# 2021-06-02.net
KiCad netlist of a schematic drawn in EasyEDA
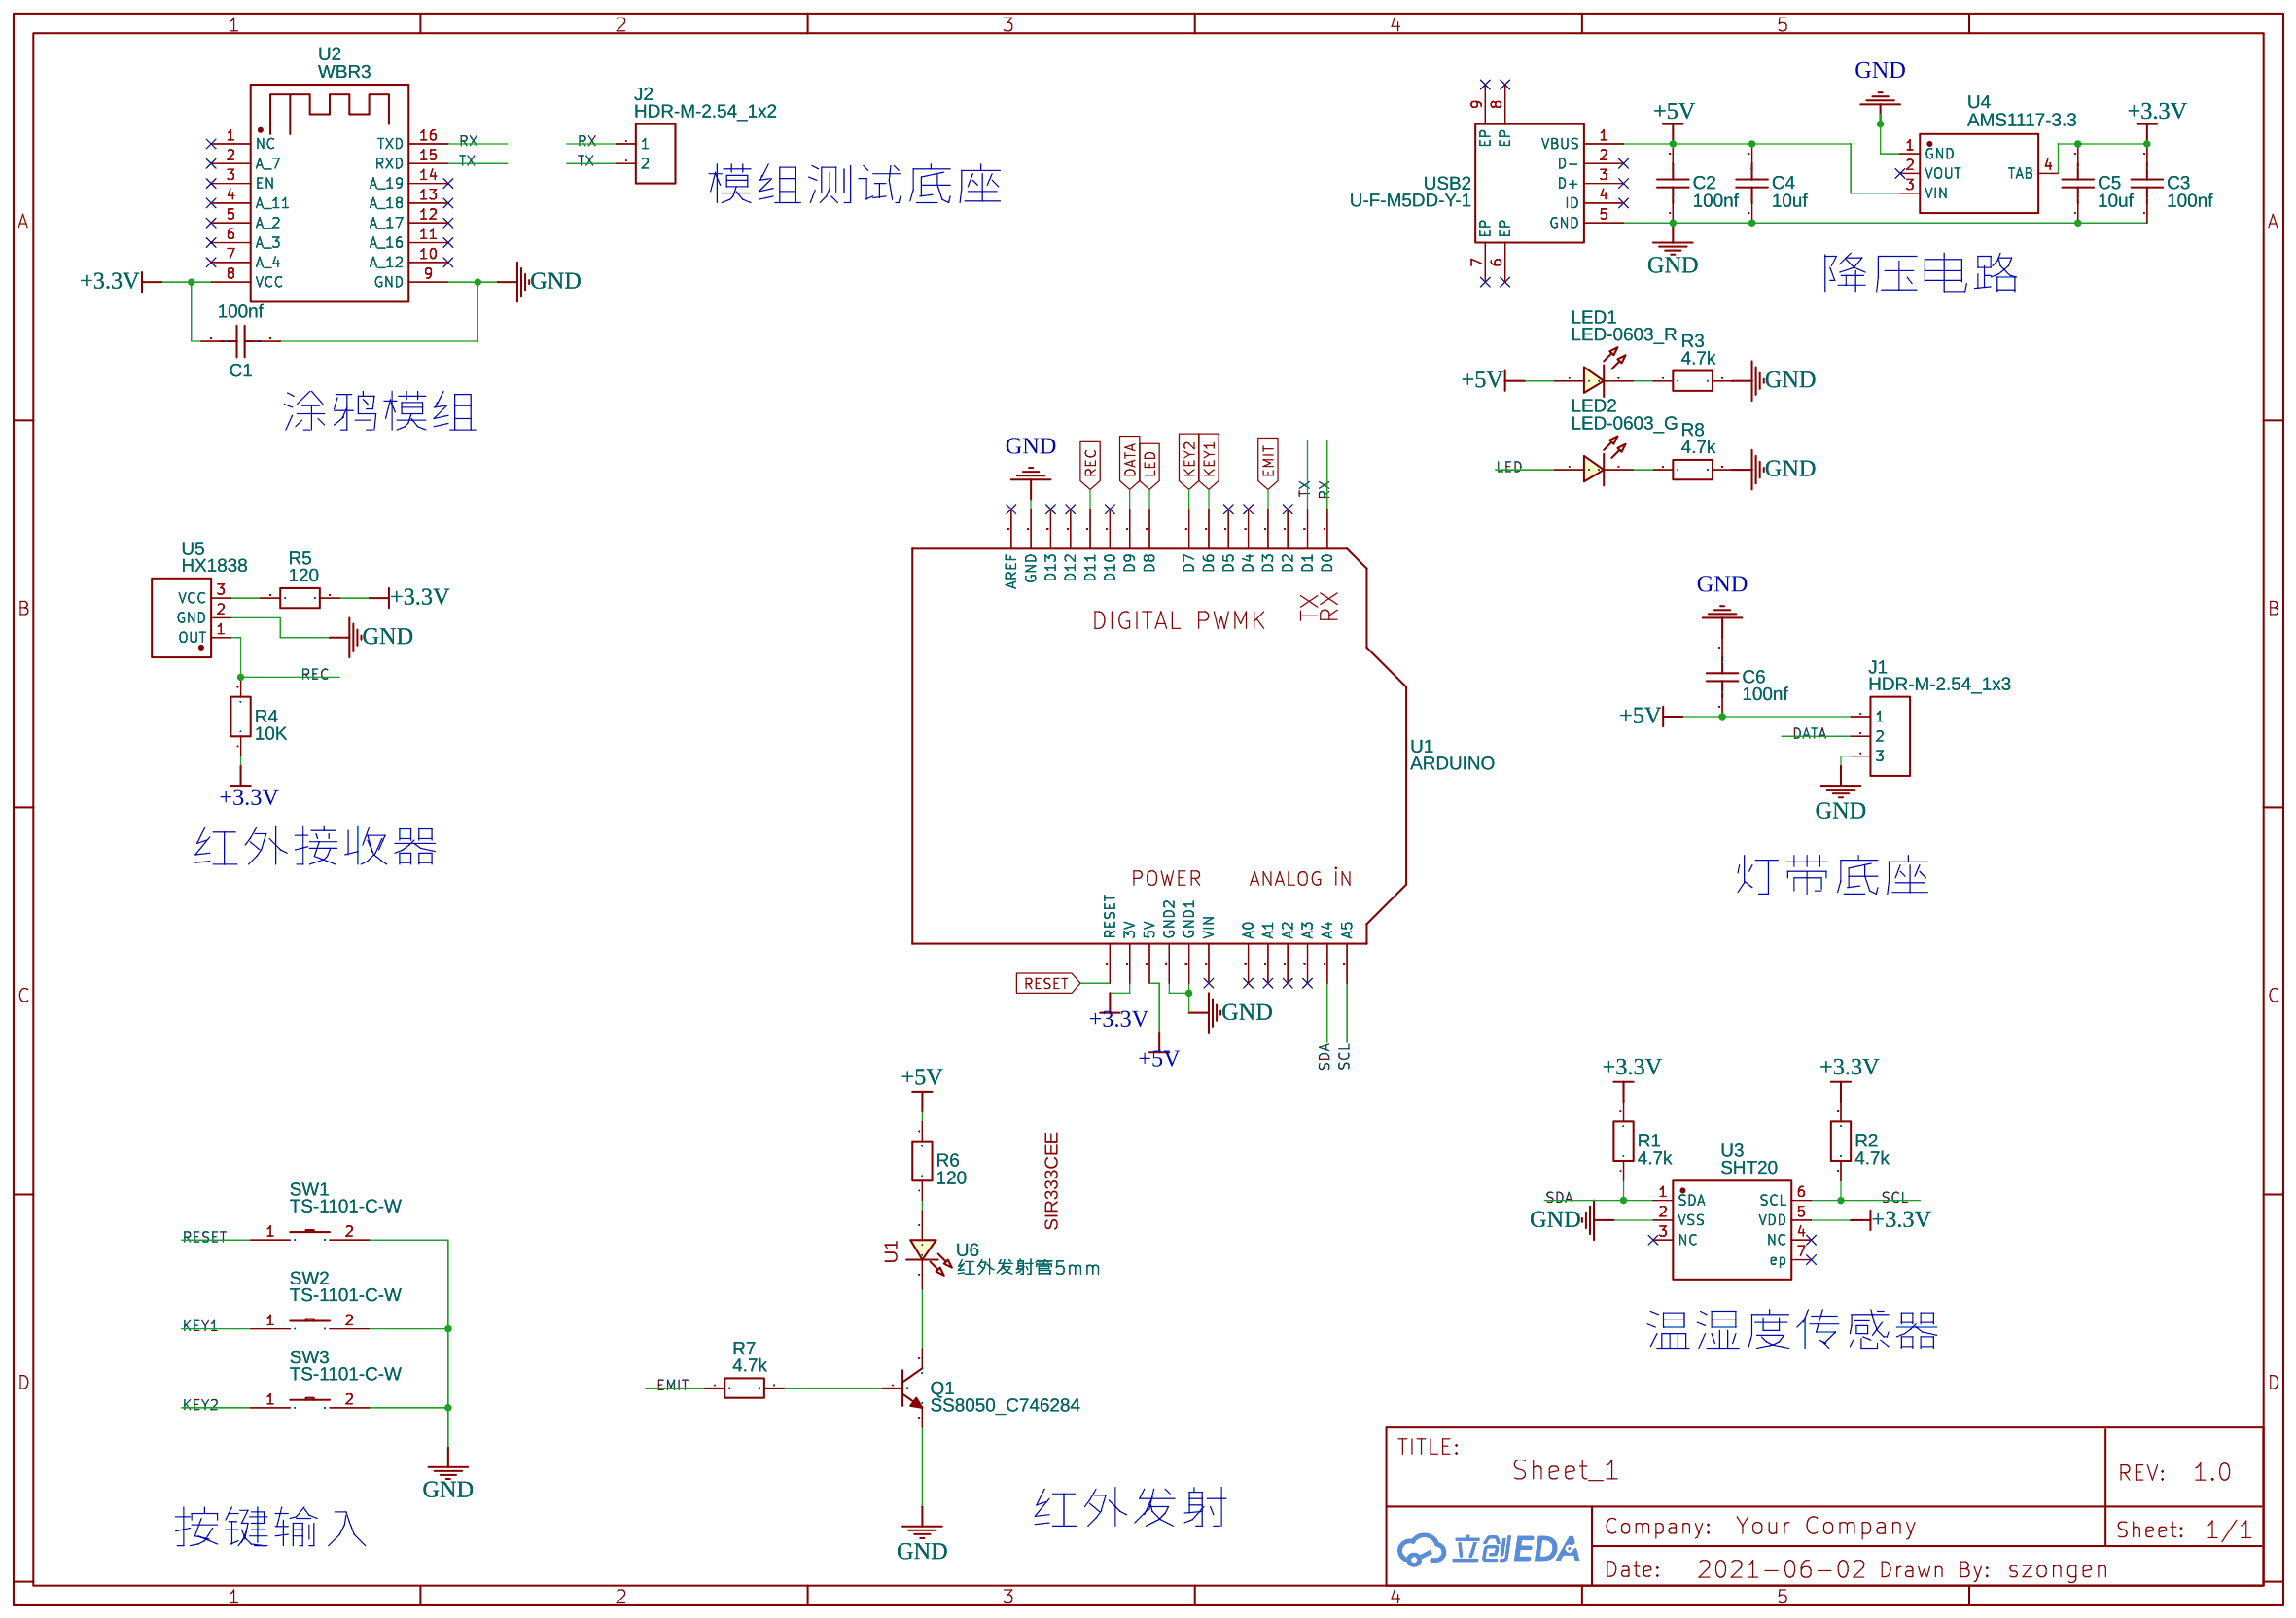
[diagram p0: schematic sheet]

(export (version "E")
  (design (tool "Eeschema 10.0.6"))
  (components
    (comp (ref "C1") (value "100nf") (libsource (lib "") (part "C_0603_US_1")))
    (comp (ref "C2") (value "100nf") (libsource (lib "") (part "C_0603_US")))
    (comp (ref "C3") (value "100nf") (libsource (lib "") (part "C_0603_US")))
    (comp (ref "C4") (value "10uf") (libsource (lib "") (part "C_0603_US")))
    (comp (ref "C5") (value "10uf") (libsource (lib "") (part "C_0603_US")))
    (comp (ref "C6") (value "100nf") (libsource (lib "") (part "C_0603_US")))
    (comp (ref "J1")
      (value "HDR-M-2.54_1x3")
      (fields (field (name "BOM_Supplier Part") "C180248"))
      (libsource (lib "") (part "HDR-M-2.54_1x3"))
    )
    (comp (ref "J2")
      (value "HDR-M-2.54_1x2")
      (fields (field (name "BOM_Supplier Part") "C124375"))
      (libsource (lib "") (part "HDR-M-2.54_1x2"))
    )
    (comp (ref "LED1")
      (value "LED-0603_R")
      (fields
        (field (name "BOM_Manufacturer Part") "19-217/R6C-AL1M2VY/3T")
        (field (name "BOM_Supplier Part") "C72044")
      )
      (libsource (lib "") (part "LED-0603_R"))
    )
    (comp (ref "LED2")
      (value "LED-0603_G")
      (fields
        (field (name "BOM_Manufacturer Part") "19-217/GHC-YR1S2/3T")
        (field (name "BOM_Supplier Part") "C72043")
      )
      (libsource (lib "") (part "LED-0603_G"))
    )
    (comp (ref "Q1")
      (value "SS8050_C746284")
      (fields (field (name "BOM_Manufacturer Part") "SS8050") (field (name "BOM_Supplier Part") "C746284"))
      (libsource (lib "") (part "SS8050_C746284"))
    )
    (comp (ref "R1") (value "4.7k") (libsource (lib "") (part "R_0603_EU_1")))
    (comp (ref "R2") (value "4.7k") (libsource (lib "") (part "R_0603_EU_1")))
    (comp (ref "R3") (value "4.7k") (libsource (lib "") (part "R_0603_EU")))
    (comp (ref "R4") (value "10K") (libsource (lib "") (part "R_0805_EU_1")))
    (comp (ref "R5") (value "120") (libsource (lib "") (part "R_0805_EU")))
    (comp (ref "R6") (value "120") (libsource (lib "") (part "R_0805_EU_1")))
    (comp (ref "R7") (value "4.7k") (libsource (lib "") (part "R_0805_EU")))
    (comp (ref "R8") (value "4.7k") (libsource (lib "") (part "R_0603_EU")))
    (comp (ref "SW1")
      (value "TS-1101-C-W")
      (fields (field (name "BOM_Supplier Part") "C318938"))
      (libsource (lib "") (part "TS-1101-C-W"))
    )
    (comp (ref "SW2")
      (value "TS-1101-C-W")
      (fields (field (name "BOM_Supplier Part") "C318938"))
      (libsource (lib "") (part "TS-1101-C-W"))
    )
    (comp (ref "SW3")
      (value "TS-1101-C-W")
      (fields (field (name "BOM_Supplier Part") "C318938"))
      (libsource (lib "") (part "TS-1101-C-W"))
    )
    (comp (ref "U1") (value "ARDUINO") (libsource (lib "") (part "ARDUINO")))
    (comp (ref "U2") (value "WBR3") (libsource (lib "") (part "WBR3")))
    (comp (ref "U3")
      (value "SHT20")
      (fields (field (name "BOM_Supplier Part") "C53865"))
      (libsource (lib "") (part "SHT20"))
    )
    (comp (ref "U4")
      (value "AMS1117-3.3")
      (fields (field (name "BOM_Supplier Part") "C351784"))
      (libsource (lib "") (part "AMS1117-3.3_C351784"))
    )
    (comp (ref "U5")
      (value "HX1838")
      (fields (field (name "BOM_Manufacturer Part") "0"))
      (libsource (lib "") (part "HX1838"))
    )
    (comp (ref "U6") (value "红外发射管5mm") (libsource (lib "") (part "红外发射管5mm")))
    (comp (ref "USB2")
      (value "U-F-M5DD-Y-1")
      (fields (field (name "BOM_Supplier Part") "C91467"))
      (libsource (lib "") (part "U-F-M5DD-Y-1"))
    )
  )
  (nets
    (net (code "1") (name "+3.3V") (class "Default")
      (node (ref "C1") (pin "1") (pinfunction "1_1") (pintype "unspecified"))
      (node (ref "C3") (pin "2") (pinfunction "2_2") (pintype "unspecified"))
      (node (ref "C5") (pin "2") (pinfunction "2_2") (pintype "unspecified"))
      (node (ref "R1") (pin "2") (pinfunction "2_2") (pintype "unspecified"))
      (node (ref "R2") (pin "2") (pinfunction "2_2") (pintype "unspecified"))
      (node (ref "R4") (pin "1") (pinfunction "1_1") (pintype "unspecified"))
      (node (ref "R5") (pin "2") (pinfunction "2_2") (pintype "unspecified"))
      (node (ref "U1") (pin "3V") (pinfunction "3V_3V") (pintype "passive"))
      (node (ref "U2") (pin "8") (pinfunction "VCC_8") (pintype "unspecified"))
      (node (ref "U3") (pin "5") (pinfunction "VDD_5") (pintype "unspecified"))
      (node (ref "U4") (pin "4") (pinfunction "TAB_4") (pintype "unspecified"))
    )
    (net (code "2") (name "+5V") (class "Default")
      (node (ref "C2") (pin "2") (pinfunction "2_2") (pintype "unspecified"))
      (node (ref "C4") (pin "2") (pinfunction "2_2") (pintype "unspecified"))
      (node (ref "C6") (pin "1") (pinfunction "1_1") (pintype "unspecified"))
      (node (ref "J1") (pin "1") (pinfunction "1_1") (pintype "input"))
      (node (ref "LED1") (pin "1") (pinfunction "1_1") (pintype "unspecified"))
      (node (ref "R6") (pin "2") (pinfunction "2_2") (pintype "unspecified"))
      (node (ref "U1") (pin "5V") (pinfunction "5V_5V") (pintype "passive"))
      (node (ref "U4") (pin "3") (pinfunction "VIN_3") (pintype "unspecified"))
      (node (ref "USB2") (pin "1") (pinfunction "VBUS_1") (pintype "unspecified"))
    )
    (net (code "3") (name "/RX") (class "Default")
      (node (ref "J2") (pin "1") (pinfunction "1_1") (pintype "unspecified"))
      (node (ref "U1") (pin "D0") (pinfunction "D0_D0") (pintype "unspecified"))
      (node (ref "U2") (pin "16") (pinfunction "TXD_16") (pintype "unspecified"))
    )
    (net (code "4") (name "/SCL") (class "Default")
      (node (ref "R2") (pin "1") (pinfunction "1_1") (pintype "unspecified"))
      (node (ref "U1") (pin "A5") (pinfunction "A5_A5") (pintype "unspecified"))
      (node (ref "U3") (pin "6") (pinfunction "SCL_6") (pintype "unspecified"))
    )
    (net (code "5") (name "/SDA") (class "Default")
      (node (ref "R1") (pin "1") (pinfunction "1_1") (pintype "unspecified"))
      (node (ref "U1") (pin "A4") (pinfunction "A4_A4") (pintype "unspecified"))
      (node (ref "U3") (pin "1") (pinfunction "SDA_1") (pintype "unspecified"))
    )
    (net (code "6") (name "/TX") (class "Default")
      (node (ref "J2") (pin "2") (pinfunction "2_2") (pintype "unspecified"))
      (node (ref "U1") (pin "D1") (pinfunction "D1_D1") (pintype "unspecified"))
      (node (ref "U2") (pin "15") (pinfunction "RXD_15") (pintype "unspecified"))
    )
    (net (code "7") (name "DATA") (class "Default")
      (node (ref "J1") (pin "2") (pinfunction "2_2") (pintype "input"))
      (node (ref "U1") (pin "D9") (pinfunction "D9_D9") (pintype "unspecified"))
    )
    (net (code "8") (name "EMIT") (class "Default")
      (node (ref "R7") (pin "1") (pinfunction "1_1") (pintype "unspecified"))
      (node (ref "U1") (pin "D3") (pinfunction "D3_D3") (pintype "unspecified"))
    )
    (net (code "9") (name "GND") (class "Default")
      (node (ref "C1") (pin "2") (pinfunction "2_2") (pintype "unspecified"))
      (node (ref "C2") (pin "1") (pinfunction "1_1") (pintype "unspecified"))
      (node (ref "C3") (pin "1") (pinfunction "1_1") (pintype "unspecified"))
      (node (ref "C4") (pin "1") (pinfunction "1_1") (pintype "unspecified"))
      (node (ref "C5") (pin "1") (pinfunction "1_1") (pintype "unspecified"))
      (node (ref "C6") (pin "2") (pinfunction "2_2") (pintype "unspecified"))
      (node (ref "J1") (pin "3") (pinfunction "3_3") (pintype "input"))
      (node (ref "Q1") (pin "2") (pinfunction "E_2") (pintype "unspecified"))
      (node (ref "R3") (pin "2") (pinfunction "2_2") (pintype "unspecified"))
      (node (ref "R8") (pin "2") (pinfunction "2_2") (pintype "unspecified"))
      (node (ref "SW1") (pin "2") (pinfunction "2_2") (pintype "unspecified"))
      (node (ref "SW2") (pin "2") (pinfunction "2_2") (pintype "unspecified"))
      (node (ref "SW3") (pin "2") (pinfunction "2_2") (pintype "unspecified"))
      (node (ref "U1") (pin "GND") (pinfunction "GND_GND") (pintype "passive"))
      (node (ref "U1") (pin "GND1") (pinfunction "GND1_GND1") (pintype "passive"))
      (node (ref "U1") (pin "GND2") (pinfunction "GND2_GND2") (pintype "passive"))
      (node (ref "U2") (pin "9") (pinfunction "GND_9") (pintype "unspecified"))
      (node (ref "U3") (pin "2") (pinfunction "VSS_2") (pintype "unspecified"))
      (node (ref "U4") (pin "1") (pinfunction "GND_1") (pintype "unspecified"))
      (node (ref "U5") (pin "2") (pinfunction "GND_2") (pintype "unspecified"))
      (node (ref "USB2") (pin "5") (pinfunction "GND_5") (pintype "unspecified"))
    )
    (net (code "10") (name "KEY1") (class "Default")
      (node (ref "SW2") (pin "1") (pinfunction "1_1") (pintype "unspecified"))
      (node (ref "U1") (pin "D6") (pinfunction "D6_D6") (pintype "unspecified"))
    )
    (net (code "11") (name "KEY2") (class "Default")
      (node (ref "SW3") (pin "1") (pinfunction "1_1") (pintype "unspecified"))
      (node (ref "U1") (pin "D7") (pinfunction "D7_D7") (pintype "unspecified"))
    )
    (net (code "12") (name "LED") (class "Default")
      (node (ref "LED2") (pin "1") (pinfunction "1_1") (pintype "unspecified"))
      (node (ref "U1") (pin "D8") (pinfunction "D8_D8") (pintype "unspecified"))
    )
    (net (code "13") (name "Net-(LED1-Pad2)") (class "Default")
      (node (ref "LED1") (pin "2") (pinfunction "2_2") (pintype "unspecified"))
      (node (ref "R3") (pin "1") (pinfunction "1_1") (pintype "unspecified"))
    )
    (net (code "14") (name "Net-(LED2-Pad2)") (class "Default")
      (node (ref "LED2") (pin "2") (pinfunction "2_2") (pintype "unspecified"))
      (node (ref "R8") (pin "1") (pinfunction "1_1") (pintype "unspecified"))
    )
    (net (code "15") (name "Net-(Q1-B)") (class "Default")
      (node (ref "Q1") (pin "1") (pinfunction "B_1") (pintype "unspecified"))
      (node (ref "R7") (pin "2") (pinfunction "2_2") (pintype "unspecified"))
    )
    (net (code "16") (name "Net-(Q1-C)") (class "Default")
      (node (ref "Q1") (pin "3") (pinfunction "C_3") (pintype "unspecified"))
      (node (ref "U6") (pin "2") (pinfunction "C_2") (pintype "unspecified"))
    )
    (net (code "17") (name "Net-(U5-VCC)") (class "Default")
      (node (ref "R5") (pin "1") (pinfunction "1_1") (pintype "unspecified"))
      (node (ref "U5") (pin "3") (pinfunction "VCC_3") (pintype "unspecified"))
    )
    (net (code "18") (name "Net-(U6-A)") (class "Default")
      (node (ref "R6") (pin "1") (pinfunction "1_1") (pintype "unspecified"))
      (node (ref "U6") (pin "1") (pinfunction "A_1") (pintype "unspecified"))
    )
    (net (code "19") (name "REC") (class "Default")
      (node (ref "R4") (pin "2") (pinfunction "2_2") (pintype "unspecified"))
      (node (ref "U1") (pin "D11") (pinfunction "D11_D11") (pintype "unspecified"))
      (node (ref "U5") (pin "1") (pinfunction "OUT_1") (pintype "unspecified"))
    )
    (net (code "20") (name "RESET") (class "Default")
      (node (ref "SW1") (pin "1") (pinfunction "1_1") (pintype "unspecified"))
      (node (ref "U1") (pin "RESET") (pinfunction "RESET_RESET") (pintype "unspecified"))
    )
    (net (code "21") (name "unconnected-(U1-PadA0)") (class "Default")
      (node (ref "U1") (pin "A0") (pinfunction "A0_A0") (pintype "unspecified+no_connect"))
    )
    (net (code "22") (name "unconnected-(U1-PadA1)") (class "Default")
      (node (ref "U1") (pin "A1") (pinfunction "A1_A1") (pintype "unspecified+no_connect"))
    )
    (net (code "23") (name "unconnected-(U1-PadA2)") (class "Default")
      (node (ref "U1") (pin "A2") (pinfunction "A2_A2") (pintype "unspecified+no_connect"))
    )
    (net (code "24") (name "unconnected-(U1-PadA3)") (class "Default")
      (node (ref "U1") (pin "A3") (pinfunction "A3_A3") (pintype "unspecified+no_connect"))
    )
    (net (code "25") (name "unconnected-(U1-PadAREF)") (class "Default")
      (node (ref "U1") (pin "AREF") (pinfunction "AREF_AREF") (pintype "unspecified+no_connect"))
    )
    (net (code "26") (name "unconnected-(U1-PadD2)") (class "Default")
      (node (ref "U1") (pin "D2") (pinfunction "D2_D2") (pintype "unspecified+no_connect"))
    )
    (net (code "27") (name "unconnected-(U1-PadD4)") (class "Default")
      (node (ref "U1") (pin "D4") (pinfunction "D4_D4") (pintype "unspecified+no_connect"))
    )
    (net (code "28") (name "unconnected-(U1-PadD5)") (class "Default")
      (node (ref "U1") (pin "D5") (pinfunction "D5_D5") (pintype "unspecified+no_connect"))
    )
    (net (code "29") (name "unconnected-(U1-PadD10)") (class "Default")
      (node (ref "U1") (pin "D10") (pinfunction "D10_D10") (pintype "unspecified+no_connect"))
    )
    (net (code "30") (name "unconnected-(U1-PadD12)") (class "Default")
      (node (ref "U1") (pin "D12") (pinfunction "D12_D12") (pintype "unspecified+no_connect"))
    )
    (net (code "31") (name "unconnected-(U1-PadD13)") (class "Default")
      (node (ref "U1") (pin "D13") (pinfunction "D13_D13") (pintype "unspecified+no_connect"))
    )
    (net (code "32") (name "unconnected-(U1-PadVIN)") (class "Default")
      (node (ref "U1") (pin "VIN") (pinfunction "VIN_VIN") (pintype "passive+no_connect"))
    )
    (net (code "33") (name "unconnected-(U2-A_2-Pad5)") (class "Default")
      (node (ref "U2") (pin "5") (pinfunction "A_2_5") (pintype "unspecified+no_connect"))
    )
    (net (code "34") (name "unconnected-(U2-A_3-Pad6)") (class "Default")
      (node (ref "U2") (pin "6") (pinfunction "A_3_6") (pintype "unspecified+no_connect"))
    )
    (net (code "35") (name "unconnected-(U2-A_4-Pad7)") (class "Default")
      (node (ref "U2") (pin "7") (pinfunction "A_4_7") (pintype "unspecified+no_connect"))
    )
    (net (code "36") (name "unconnected-(U2-A_7-Pad2)") (class "Default")
      (node (ref "U2") (pin "2") (pinfunction "A_7_2") (pintype "unspecified+no_connect"))
    )
    (net (code "37") (name "unconnected-(U2-A_11-Pad4)") (class "Default")
      (node (ref "U2") (pin "4") (pinfunction "A_11_4") (pintype "unspecified+no_connect"))
    )
    (net (code "38") (name "unconnected-(U2-A_12-Pad10)") (class "Default")
      (node (ref "U2") (pin "10") (pinfunction "A_12_10") (pintype "unspecified+no_connect"))
    )
    (net (code "39") (name "unconnected-(U2-A_16-Pad11)") (class "Default")
      (node (ref "U2") (pin "11") (pinfunction "A_16_11") (pintype "unspecified+no_connect"))
    )
    (net (code "40") (name "unconnected-(U2-A_17-Pad12)") (class "Default")
      (node (ref "U2") (pin "12") (pinfunction "A_17_12") (pintype "unspecified+no_connect"))
    )
    (net (code "41") (name "unconnected-(U2-A_18-Pad13)") (class "Default")
      (node (ref "U2") (pin "13") (pinfunction "A_18_13") (pintype "unspecified+no_connect"))
    )
    (net (code "42") (name "unconnected-(U2-A_19-Pad14)") (class "Default")
      (node (ref "U2") (pin "14") (pinfunction "A_19_14") (pintype "unspecified+no_connect"))
    )
    (net (code "43") (name "unconnected-(U2-EN-Pad3)") (class "Default")
      (node (ref "U2") (pin "3") (pinfunction "EN_3") (pintype "unspecified+no_connect"))
    )
    (net (code "44") (name "unconnected-(U2-NC-Pad1)") (class "Default")
      (node (ref "U2") (pin "1") (pinfunction "NC_1") (pintype "unspecified+no_connect"))
    )
    (net (code "45") (name "unconnected-(U3-NC-Pad3)") (class "Default")
      (node (ref "U3") (pin "3") (pinfunction "NC_3") (pintype "unspecified+no_connect"))
    )
    (net (code "46") (name "unconnected-(U3-NC-Pad4)") (class "Default")
      (node (ref "U3") (pin "4") (pinfunction "NC_4") (pintype "unspecified+no_connect"))
    )
    (net (code "47") (name "unconnected-(U3-ep-Pad7)") (class "Default")
      (node (ref "U3") (pin "7") (pinfunction "ep_7") (pintype "unspecified+no_connect"))
    )
    (net (code "48") (name "unconnected-(U4-VOUT-Pad2)") (class "Default")
      (node (ref "U4") (pin "2") (pinfunction "VOUT_2") (pintype "unspecified+no_connect"))
    )
    (net (code "49") (name "unconnected-(USB2-D+-Pad3)") (class "Default")
      (node (ref "USB2") (pin "3") (pinfunction "D+_3") (pintype "unspecified+no_connect"))
    )
    (net (code "50") (name "unconnected-(USB2-D--Pad2)") (class "Default")
      (node (ref "USB2") (pin "2") (pinfunction "D-_2") (pintype "unspecified+no_connect"))
    )
    (net (code "51") (name "unconnected-(USB2-EP-Pad6)") (class "Default")
      (node (ref "USB2") (pin "6") (pinfunction "EP_6") (pintype "unspecified+no_connect"))
    )
    (net (code "52") (name "unconnected-(USB2-EP-Pad7)") (class "Default")
      (node (ref "USB2") (pin "7") (pinfunction "EP_7") (pintype "unspecified+no_connect"))
    )
    (net (code "53") (name "unconnected-(USB2-EP-Pad8)") (class "Default")
      (node (ref "USB2") (pin "8") (pinfunction "EP_8") (pintype "unspecified+no_connect"))
    )
    (net (code "54") (name "unconnected-(USB2-EP-Pad9)") (class "Default")
      (node (ref "USB2") (pin "9") (pinfunction "EP_9") (pintype "unspecified+no_connect"))
    )
    (net (code "55") (name "unconnected-(USB2-ID-Pad4)") (class "Default")
      (node (ref "USB2") (pin "4") (pinfunction "ID_4") (pintype "unspecified+no_connect"))
    )
  )
)
